# F427_IMU_Power_Supply.net
KiCad netlist of a schematic drawn in Altium Designer
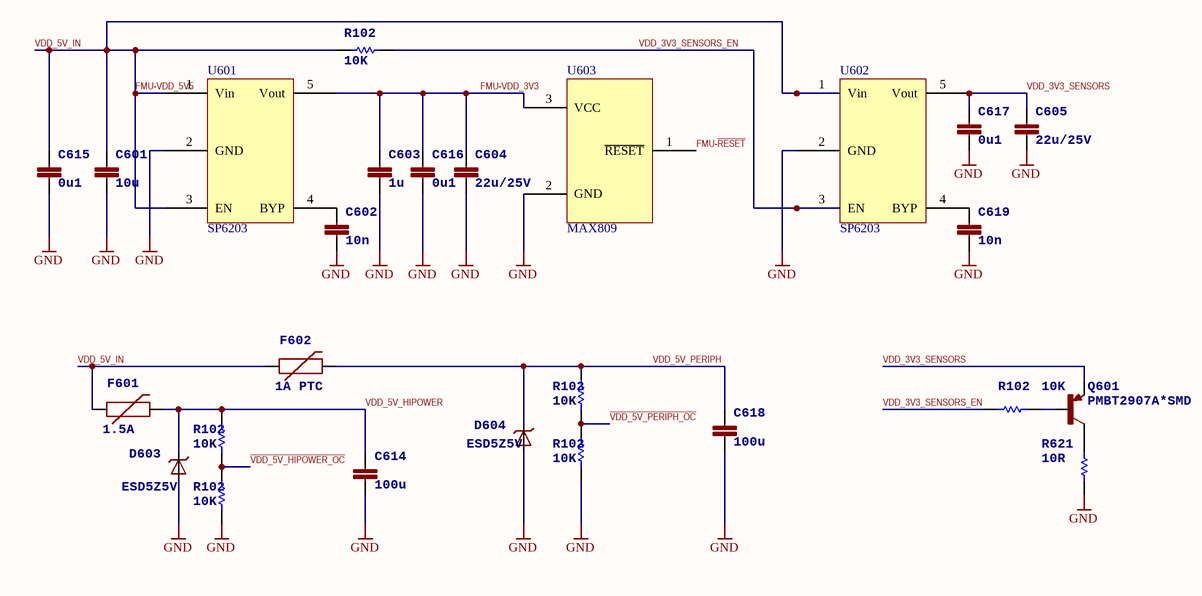
[diagram p0: F427&IMU Power Supply.SchDoc]

(export (version "E")
  (design (tool "Eeschema 10.0.6"))
  (components
    (comp (ref "C601")
      (value "10u")
      (footprint "0805-CAP")
      (description "<b>Capacitor</b>\nStandard 0603 ceramic capacitor, and 0.1\" leaded capacitor.")
      (fields
        (field (name "PARTNO") "CL21A106KAYNNNE")
        (field (name ">NAME") "C601")
        (field (name ">VALUE") "10u")
      )
      (libsource (lib "pixhawk2") (part "CAP0805"))
    )
    (comp (ref "C602")
      (value "10n")
      (footprint "0603-CAP")
      (description "<b>Capacitor</b>\nStandard 0603 ceramic capacitor, and 0.1\" leaded capacitor.")
      (fields
        (field (name "PARTNO") "CL21A106KAYNNNE")
        (field (name ">NAME") "C602")
        (field (name ">VALUE") "10n")
      )
      (libsource (lib "pixhawk2") (part "CAP0805"))
    )
    (comp (ref "C603")
      (value "1u")
      (footprint "0603-CAP")
      (description "<b>Capacitor</b>\nStandard 0603 ceramic capacitor, and 0.1\" leaded capacitor.")
      (fields
        (field (name "PARTNO") "CC0603ZRY5V7BB105")
        (field (name ">NAME") "C603")
        (field (name ">VALUE") "1u")
      )
      (libsource (lib "pixhawk2") (part "CAP0603"))
    )
    (comp (ref "C604")
      (value "22u/25V")
      (footprint "0805-CAP")
      (description "<b>Capacitor</b>\nStandard 0603 ceramic capacitor, and 0.1\" leaded capacitor.")
      (fields
        (field (name "PARTNO") "CL21A226MAQNNNE")
        (field (name ">NAME") "C604")
        (field (name ">VALUE") "22u/25V")
      )
      (libsource (lib "pixhawk2") (part "CAP0805"))
    )
    (comp (ref "C605")
      (value "22u/25V")
      (footprint "0805-CAP")
      (description "<b>Capacitor</b>\nStandard 0603 ceramic capacitor, and 0.1\" leaded capacitor.")
      (fields
        (field (name "PARTNO") "CL21A226MAQNNNE")
        (field (name ">NAME") "C605")
        (field (name ">VALUE") "22u/25V")
      )
      (libsource (lib "pixhawk2") (part "CAP0805"))
    )
    (comp (ref "C614")
      (value "100u")
      (footprint "1206-CAP")
      (description "<b>Capacitor</b>\nStandard 0603 ceramic capacitor, and 0.1\" leaded capacitor.")
      (fields
        (field (name "PARTNO") "C3216X5R1A107M160AC")
        (field (name ">NAME") "C614")
        (field (name ">VALUE") "100u")
      )
      (libsource (lib "pixhawk2") (part "CAP1206"))
    )
    (comp (ref "C615")
      (value "0u1")
      (footprint "0603-CAP")
      (description "<b>Capacitor</b>\nStandard 0603 ceramic capacitor, and 0.1\" leaded capacitor.")
      (fields
        (field (name "PARTNO") "CC0402ZRY5V7BB104")
        (field (name ">NAME") "C615")
        (field (name ">VALUE") "0u1")
      )
      (libsource (lib "pixhawk2") (part "CAP0402"))
    )
    (comp (ref "C616")
      (value "0u1")
      (footprint "0603-CAP")
      (description "<b>Capacitor</b>\nStandard 0603 ceramic capacitor, and 0.1\" leaded capacitor.")
      (fields
        (field (name "PARTNO") "CC0402ZRY5V7BB104")
        (field (name ">NAME") "C616")
        (field (name ">VALUE") "0u1")
      )
      (libsource (lib "pixhawk2") (part "CAP0402"))
    )
    (comp (ref "C617")
      (value "0u1")
      (footprint "0603-CAP")
      (description "<b>Capacitor</b>\nStandard 0603 ceramic capacitor, and 0.1\" leaded capacitor.")
      (fields
        (field (name "PARTNO") "CC0402ZRY5V7BB104")
        (field (name ">NAME") "C617")
        (field (name ">VALUE") "0u1")
      )
      (libsource (lib "pixhawk2") (part "CAP0402"))
    )
    (comp (ref "C618")
      (value "100u")
      (footprint "1206-CAP")
      (description "<b>Capacitor</b>\nStandard 0603 ceramic capacitor, and 0.1\" leaded capacitor.")
      (fields
        (field (name "PARTNO") "C3216X5R1A107M160AC")
        (field (name ">NAME") "C618")
        (field (name ">VALUE") "100u")
      )
      (libsource (lib "pixhawk2") (part "CAP1206"))
    )
    (comp (ref "C619")
      (value "10n")
      (footprint "0603-CAP")
      (description "<b>Capacitor</b>\nStandard 0603 ceramic capacitor, and 0.1\" leaded capacitor.")
      (fields
        (field (name "PARTNO") "CL21A106KAYNNNE")
        (field (name ">NAME") "C619")
        (field (name ">VALUE") "10n")
      )
      (libsource (lib "pixhawk2") (part "CAP0805"))
    )
    (comp (ref "D603") (value "ESD5Z5V") (footprint "SOD523") (libsource (lib "pixhawk2") (part "DIODE-TVS")))
    (comp (ref "D604") (value "ESD5Z5V") (footprint "SOD523") (libsource (lib "pixhawk2") (part "DIODE-TVS")))
    (comp (ref "F601")
      (value "2A PTC")
      (footprint "PTC-1206")
      (description "<b>Resettable Fuse PTC</b>\nResettable Fuse. Spark Fun Electronics SKU : COM-08357")
      (fields (field (name ">NAME") "F601") (field (name ">VALUE") "1.5A"))
      (libsource (lib "pixhawk2") (part "PTCSMD"))
    )
    (comp (ref "F602")
      (value "1A PTC")
      (footprint "PTC-1206")
      (description "<b>Resettable Fuse PTC</b>\nResettable Fuse. Spark Fun Electronics SKU : COM-08357")
      (fields (field (name ">NAME") "F602") (field (name ">VALUE") "1A PTC"))
      (libsource (lib "pixhawk2") (part "PTCSMD"))
    )
    (comp (ref "Q601")
      (value "PMBT2907A*SMD")
      (footprint "SOT23-BEC")
      (description "<b>PNP Transistror</b>")
      (libsource (lib "transistor-pnp") (part "MMBT3906*SMD"))
    )
    (comp (ref "R602")
      (value "10K")
      (footprint "0603-RES")
      (fields
        (field (name "PARTNO") "RC0402FR-0710KL")
        (field (name ">NAME") "R102")
        (field (name ">VALUE") "10K")
      )
      (libsource (lib "PX4") (part "RESISTOR0402-RES"))
    )
    (comp (ref "R603")
      (value "10K")
      (footprint "0603-RES")
      (fields
        (field (name "PARTNO") "RC0402FR-0710KL")
        (field (name ">NAME") "R102")
        (field (name ">VALUE") "10K")
      )
      (libsource (lib "PX4") (part "RESISTOR0402-RES"))
    )
    (comp (ref "R604")
      (value "10K")
      (footprint "0603-RES")
      (fields
        (field (name "PARTNO") "RC0402FR-0710KL")
        (field (name ">NAME") "R102")
        (field (name ">VALUE") "10K")
      )
      (libsource (lib "PX4") (part "RESISTOR0402-RES"))
    )
    (comp (ref "R616")
      (value "10K")
      (footprint "0603-RES")
      (fields
        (field (name "PARTNO") "RC0402FR-0710KL")
        (field (name ">NAME") "R102")
        (field (name ">VALUE") "10K")
      )
      (libsource (lib "PX4") (part "RESISTOR0402-RES"))
    )
    (comp (ref "R617")
      (value "10K")
      (footprint "0603-RES")
      (fields
        (field (name "PARTNO") "RC0402FR-0710KL")
        (field (name ">NAME") "R102")
        (field (name ">VALUE") "10K")
      )
      (libsource (lib "PX4") (part "RESISTOR0402-RES"))
    )
    (comp (ref "R620")
      (value "10K")
      (footprint "0603-RES")
      (fields
        (field (name "PARTNO") "RC0402FR-0710KL")
        (field (name ">NAME") "R102")
        (field (name ">VALUE") "10K")
      )
      (libsource (lib "PX4") (part "RESISTOR0402-RES"))
    )
    (comp (ref "R621")
      (value "10R")
      (footprint "0603-RES")
      (fields
        (field (name "PARTNO") "RC1608J100CS")
        (field (name ">NAME") "R621")
        (field (name ">VALUE") "10R")
      )
      (libsource (lib "PX4") (part "RESISTOR0603-RES"))
    )
    (comp (ref "U601")
      (value "SP6203")
      (footprint "SOT23-5")
      (description "LDO with reset")
      (libsource (lib "PX4") (part "SP6203"))
    )
    (comp (ref "U602")
      (value "SP6203")
      (footprint "SOT23-5")
      (description "LDO with reset")
      (libsource (lib "PX4") (part "SP6203"))
    )
    (comp (ref "U603") (value "MAX809") (footprint "SOT-23B_N") (libsource (lib "PX4") (part "MAX809")))
  )
  (nets
    (net (code "1") (name "/FMU-VDD_3V3") (class "Default")
      (node (ref "C603") (pin "P$1") (pinfunction "1_P$1") (pintype "passive"))
      (node (ref "C604") (pin "P$1") (pinfunction "1_P$1") (pintype "passive"))
      (node (ref "C616") (pin "P$1") (pinfunction "1_P$1") (pintype "passive"))
      (node (ref "U601") (pin "5") (pinfunction "Vout_5") (pintype "passive"))
      (node (ref "U603") (pin "3") (pinfunction "VCC_3") (pintype "passive"))
    )
    (net (code "2") (name "/FMU-VDD_5V5") (class "Default")
      (node (ref "C601") (pin "P$1") (pinfunction "1_P$1") (pintype "passive"))
      (node (ref "C615") (pin "P$1") (pinfunction "1_P$1") (pintype "passive"))
      (node (ref "F601") (pin "1") (pinfunction "1_1") (pintype "passive"))
      (node (ref "F602") (pin "1") (pinfunction "1_1") (pintype "passive"))
      (node (ref "R603") (pin "P$1") (pinfunction "1_P$1") (pintype "passive"))
      (node (ref "U601") (pin "1") (pinfunction "Vin_1") (pintype "passive"))
      (node (ref "U601") (pin "3") (pinfunction "EN_3") (pintype "passive"))
      (node (ref "U602") (pin "1") (pinfunction "Vin_1") (pintype "passive"))
    )
    (net (code "3") (name "/FMU-~{RESET}") (class "Default")
      (node (ref "U603") (pin "1") (pinfunction "~{RESET}_1") (pintype "passive"))
    )
    (net (code "4") (name "/VDD_3V3_SENSORS") (class "Default")
      (node (ref "C605") (pin "P$1") (pinfunction "1_P$1") (pintype "passive"))
      (node (ref "C617") (pin "P$1") (pinfunction "1_P$1") (pintype "passive"))
      (node (ref "Q601") (pin "E") (pinfunction "E_E") (pintype "passive"))
      (node (ref "U602") (pin "5") (pinfunction "Vout_5") (pintype "passive"))
    )
    (net (code "5") (name "/VDD_3V3_SENSORS_EN") (class "Default")
      (node (ref "R603") (pin "P$2") (pinfunction "2_P$2") (pintype "passive"))
      (node (ref "R620") (pin "P$2") (pinfunction "2_P$2") (pintype "passive"))
      (node (ref "U602") (pin "3") (pinfunction "EN_3") (pintype "passive"))
    )
    (net (code "6") (name "/VDD_5V_HIPOWER") (class "Default")
      (node (ref "C614") (pin "P$1") (pinfunction "1_P$1") (pintype "passive"))
      (node (ref "D603") (pin "C") (pinfunction "C_C") (pintype "passive"))
      (node (ref "F601") (pin "2") (pinfunction "2_2") (pintype "passive"))
      (node (ref "R602") (pin "P$2") (pinfunction "2_P$2") (pintype "passive"))
    )
    (net (code "7") (name "/VDD_5V_PERIPH") (class "Default")
      (node (ref "C618") (pin "P$1") (pinfunction "1_P$1") (pintype "passive"))
      (node (ref "D604") (pin "C") (pinfunction "C_C") (pintype "passive"))
      (node (ref "F602") (pin "2") (pinfunction "2_2") (pintype "passive"))
      (node (ref "R604") (pin "P$2") (pinfunction "2_P$2") (pintype "passive"))
    )
    (net (code "8") (name "/~{VDD_5V_HIPOWER_OC}") (class "Default")
      (node (ref "R602") (pin "P$1") (pinfunction "1_P$1") (pintype "passive"))
      (node (ref "R617") (pin "P$1") (pinfunction "1_P$1") (pintype "passive"))
    )
    (net (code "9") (name "/~{VDD_5V_PERIPH_OC}") (class "Default")
      (node (ref "R604") (pin "P$1") (pinfunction "1_P$1") (pintype "passive"))
      (node (ref "R616") (pin "P$1") (pinfunction "1_P$1") (pintype "passive"))
    )
    (net (code "10") (name "GND") (class "Default")
      (node (ref "C601") (pin "P$2") (pinfunction "2_P$2") (pintype "passive"))
      (node (ref "C602") (pin "P$2") (pinfunction "2_P$2") (pintype "passive"))
      (node (ref "C603") (pin "P$2") (pinfunction "2_P$2") (pintype "passive"))
      (node (ref "C604") (pin "P$2") (pinfunction "2_P$2") (pintype "passive"))
      (node (ref "C605") (pin "P$2") (pinfunction "2_P$2") (pintype "passive"))
      (node (ref "C614") (pin "P$2") (pinfunction "2_P$2") (pintype "passive"))
      (node (ref "C615") (pin "P$2") (pinfunction "2_P$2") (pintype "passive"))
      (node (ref "C616") (pin "P$2") (pinfunction "2_P$2") (pintype "passive"))
      (node (ref "C617") (pin "P$2") (pinfunction "2_P$2") (pintype "passive"))
      (node (ref "C618") (pin "P$2") (pinfunction "2_P$2") (pintype "passive"))
      (node (ref "C619") (pin "P$2") (pinfunction "2_P$2") (pintype "passive"))
      (node (ref "D603") (pin "A") (pinfunction "A_A") (pintype "passive"))
      (node (ref "D604") (pin "A") (pinfunction "A_A") (pintype "passive"))
      (node (ref "R616") (pin "P$2") (pinfunction "2_P$2") (pintype "passive"))
      (node (ref "R617") (pin "P$2") (pinfunction "2_P$2") (pintype "passive"))
      (node (ref "R621") (pin "P$1") (pinfunction "1_P$1") (pintype "passive"))
      (node (ref "U601") (pin "2") (pinfunction "GND_2") (pintype "passive"))
      (node (ref "U602") (pin "2") (pinfunction "GND_2") (pintype "passive"))
      (node (ref "U603") (pin "2") (pinfunction "GND_2") (pintype "passive"))
    )
    (net (code "11") (name "Net-(C602-1)") (class "Default")
      (node (ref "C602") (pin "P$1") (pinfunction "1_P$1") (pintype "passive"))
      (node (ref "U601") (pin "4") (pinfunction "BYP_4") (pintype "passive"))
    )
    (net (code "12") (name "Net-(C619-1)") (class "Default")
      (node (ref "C619") (pin "P$1") (pinfunction "1_P$1") (pintype "passive"))
      (node (ref "U602") (pin "4") (pinfunction "BYP_4") (pintype "passive"))
    )
    (net (code "13") (name "Net-(R620-1)") (class "Default")
      (node (ref "Q601") (pin "B") (pinfunction "B_B") (pintype "passive"))
      (node (ref "R620") (pin "P$1") (pinfunction "1_P$1") (pintype "passive"))
    )
    (net (code "14") (name "Net-(R621-2)") (class "Default")
      (node (ref "Q601") (pin "C") (pinfunction "C_C") (pintype "passive"))
      (node (ref "R621") (pin "P$2") (pinfunction "2_P$2") (pintype "passive"))
    )
  )
)
